# test-sensior-platiene.net
KiCad netlist of a schematic drawn in EAGLE
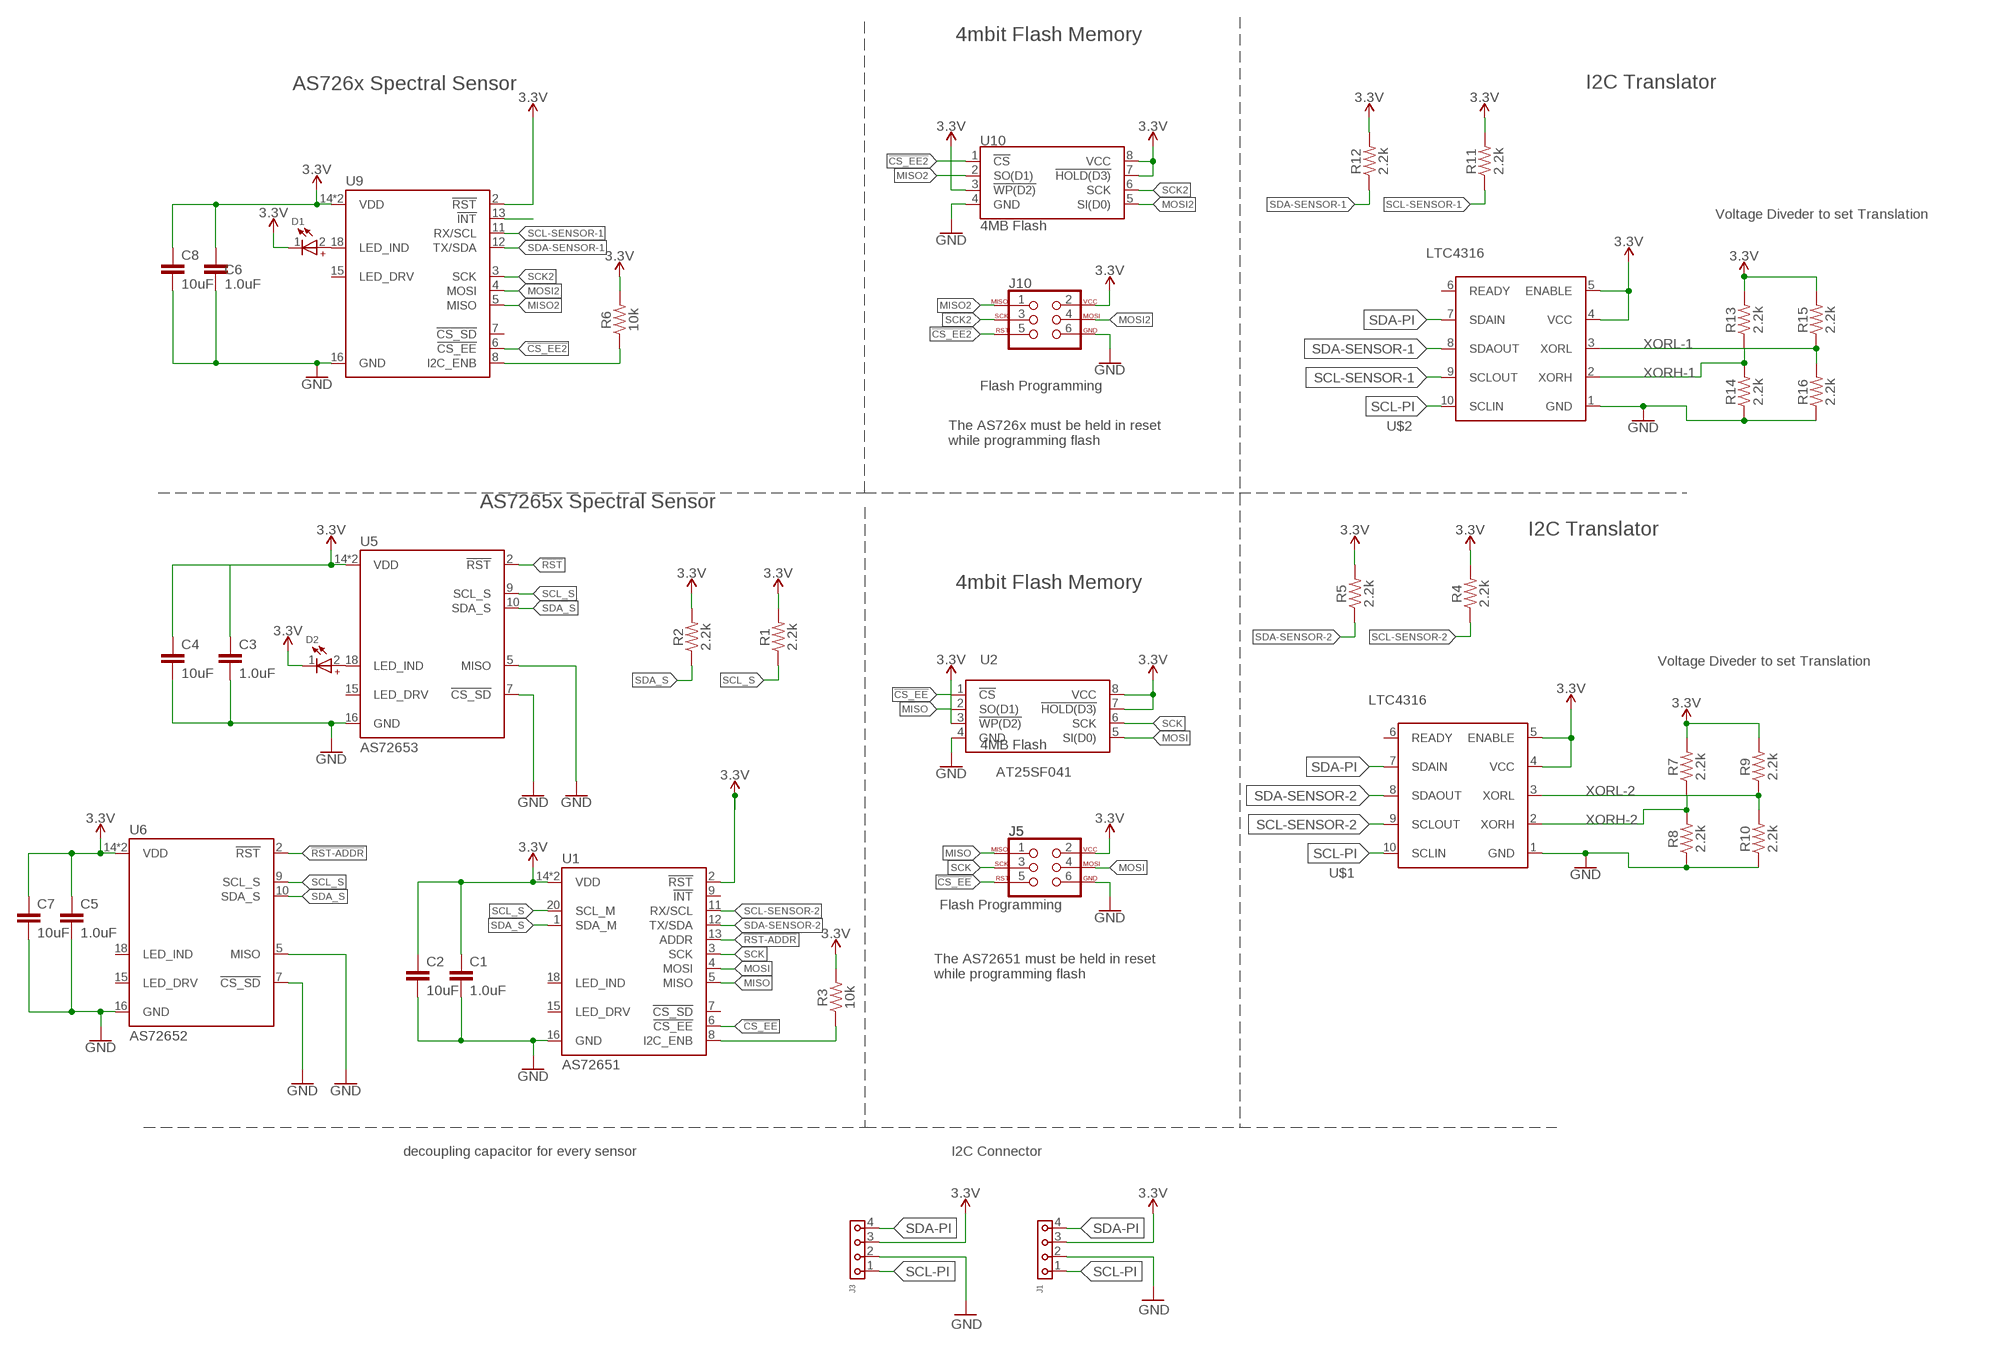
[diagram p0: schematic, sheet 1]

(export (version "E")
  (design (tool "Eeschema 10.0.6"))
  (components
    (comp (ref "C1")
      (value "1.0uF")
      (footprint "eagle-import:0603")
      (libsource (lib "eagle-import") (part "1.0UF-0603-16V-10%"))
    )
    (comp (ref "C2")
      (value "10uF")
      (footprint "eagle-import:0603")
      (libsource (lib "eagle-import") (part "10UF-0603-6.3V-20%"))
    )
    (comp (ref "C3")
      (value "1.0uF")
      (footprint "eagle-import:0603")
      (libsource (lib "eagle-import") (part "1.0UF-0603-16V-10%"))
    )
    (comp (ref "C4")
      (value "10uF")
      (footprint "eagle-import:0603")
      (libsource (lib "eagle-import") (part "10UF-0603-6.3V-20%"))
    )
    (comp (ref "C5")
      (value "1.0uF")
      (footprint "eagle-import:0603")
      (libsource (lib "eagle-import") (part "1.0UF-0603-16V-10%"))
    )
    (comp (ref "C6")
      (value "1.0uF")
      (footprint "eagle-import:0603")
      (libsource (lib "eagle-import") (part "1.0UF-0603-16V-10%"))
    )
    (comp (ref "C7")
      (value "10uF")
      (footprint "eagle-import:0603")
      (libsource (lib "eagle-import") (part "10UF-0603-6.3V-20%"))
    )
    (comp (ref "C8")
      (value "10uF")
      (footprint "eagle-import:0603")
      (libsource (lib "eagle-import") (part "10UF-0603-6.3V-20%"))
    )
    (comp (ref "D1")
      (value "WL-SMCW_1206_150120RS75000")
      (footprint "eagle-import:WL-SMCW_1206")
      (libsource (lib "eagle-import") (part "WL-SMCW_1206_150120RS75000"))
    )
    (comp (ref "D2")
      (value "WL-SMCW_1206_150120RS75000")
      (footprint "eagle-import:WL-SMCW_1206")
      (libsource (lib "eagle-import") (part "WL-SMCW_1206_150120RS75000"))
    )
    (comp (ref "J1")
      (value "6130XX11821_61300411821")
      (footprint "eagle-import:61300411821")
      (libsource (lib "eagle-import") (part "6130XX11821_61300411821"))
    )
    (comp (ref "J3")
      (value "6130XX11821_61300411821")
      (footprint "eagle-import:61300411821")
      (libsource (lib "eagle-import") (part "6130XX11821_61300411821"))
    )
    (comp (ref "J5")
      (value "Flash Programming")
      (footprint "eagle-import:2X3_TEST_POINTS")
      (libsource (lib "eagle-import") (part "AVR_SPI_PROG_3X2TESTPOINTS"))
    )
    (comp (ref "J10")
      (value "Flash Programming")
      (footprint "eagle-import:2X3_TEST_POINTS")
      (libsource (lib "eagle-import") (part "AVR_SPI_PROG_3X2TESTPOINTS"))
    )
    (comp (ref "R1")
      (value "2.2k")
      (footprint "eagle-import:0603")
      (libsource (lib "eagle-import") (part "2.2KOHM-0603-1/10W-1%"))
    )
    (comp (ref "R2")
      (value "2.2k")
      (footprint "eagle-import:0603")
      (libsource (lib "eagle-import") (part "2.2KOHM-0603-1/10W-1%"))
    )
    (comp (ref "R3")
      (value "10k")
      (footprint "eagle-import:0603")
      (libsource (lib "eagle-import") (part "10KOHM-0603-1/10W-1%"))
    )
    (comp (ref "R4")
      (value "2.2k")
      (footprint "eagle-import:0603")
      (libsource (lib "eagle-import") (part "2.2KOHM-0603-1/10W-1%"))
    )
    (comp (ref "R5")
      (value "2.2k")
      (footprint "eagle-import:0603")
      (libsource (lib "eagle-import") (part "2.2KOHM-0603-1/10W-1%"))
    )
    (comp (ref "R6")
      (value "10k")
      (footprint "eagle-import:0603")
      (libsource (lib "eagle-import") (part "10KOHM-0603-1/10W-1%"))
    )
    (comp (ref "R7")
      (value "2.2k")
      (footprint "eagle-import:0603")
      (libsource (lib "eagle-import") (part "2.2KOHM-0603-1/10W-1%"))
    )
    (comp (ref "R8")
      (value "2.2k")
      (footprint "eagle-import:0603")
      (libsource (lib "eagle-import") (part "2.2KOHM-0603-1/10W-1%"))
    )
    (comp (ref "R9")
      (value "2.2k")
      (footprint "eagle-import:0603")
      (libsource (lib "eagle-import") (part "2.2KOHM-0603-1/10W-1%"))
    )
    (comp (ref "R10")
      (value "2.2k")
      (footprint "eagle-import:0603")
      (libsource (lib "eagle-import") (part "2.2KOHM-0603-1/10W-1%"))
    )
    (comp (ref "R11")
      (value "2.2k")
      (footprint "eagle-import:0603")
      (libsource (lib "eagle-import") (part "2.2KOHM-0603-1/10W-1%"))
    )
    (comp (ref "R12")
      (value "2.2k")
      (footprint "eagle-import:0603")
      (libsource (lib "eagle-import") (part "2.2KOHM-0603-1/10W-1%"))
    )
    (comp (ref "R13")
      (value "2.2k")
      (footprint "eagle-import:0603")
      (libsource (lib "eagle-import") (part "2.2KOHM-0603-1/10W-1%"))
    )
    (comp (ref "R14")
      (value "2.2k")
      (footprint "eagle-import:0603")
      (libsource (lib "eagle-import") (part "2.2KOHM-0603-1/10W-1%"))
    )
    (comp (ref "R15")
      (value "2.2k")
      (footprint "eagle-import:0603")
      (libsource (lib "eagle-import") (part "2.2KOHM-0603-1/10W-1%"))
    )
    (comp (ref "R16")
      (value "2.2k")
      (footprint "eagle-import:0603")
      (libsource (lib "eagle-import") (part "2.2KOHM-0603-1/10W-1%"))
    )
    (comp (ref "U$1")
      (value "LTC4316")
      (footprint "eagle-import:MS-PACKAGE")
      (libsource (lib "eagle-import") (part "LTC4316"))
    )
    (comp (ref "U$2")
      (value "LTC4316")
      (footprint "eagle-import:MS-PACKAGE")
      (libsource (lib "eagle-import") (part "LTC4316"))
    )
    (comp (ref "U1")
      (value "AS72651")
      (footprint "eagle-import:LGA20")
      (libsource (lib "eagle-import") (part "AS72651"))
    )
    (comp (ref "U2")
      (value "4MB Flash")
      (footprint "eagle-import:SO08")
      (libsource (lib "eagle-import") (part "AT25SF041"))
    )
    (comp (ref "U5")
      (value "AS72653")
      (footprint "eagle-import:LGA20")
      (libsource (lib "eagle-import") (part "AS72653"))
    )
    (comp (ref "U6")
      (value "AS72652")
      (footprint "eagle-import:LGA20")
      (libsource (lib "eagle-import") (part "AS72652"))
    )
    (comp (ref "U9")
      (value "IR")
      (footprint "eagle-import:LGA20")
      (libsource (lib "eagle-import") (part "AS726XIR"))
    )
    (comp (ref "U10")
      (value "4MB Flash")
      (footprint "eagle-import:SO08")
      (libsource (lib "eagle-import") (part "AT25SF041"))
    )
  )
  (nets
    (net (code "1") (name "/XORH-1") (class "Default")
      (node (ref "R13") (pin "1") (pinfunction "1_1") (pintype "passive"))
      (node (ref "R14") (pin "2") (pinfunction "2_2") (pintype "passive"))
      (node (ref "U$2") (pin "2") (pinfunction "XORH_2") (pintype "bidirectional"))
    )
    (net (code "2") (name "/XORH-2") (class "Default")
      (node (ref "R7") (pin "1") (pinfunction "1_1") (pintype "passive"))
      (node (ref "R8") (pin "2") (pinfunction "2_2") (pintype "passive"))
      (node (ref "U$1") (pin "2") (pinfunction "XORH_2") (pintype "bidirectional"))
    )
    (net (code "3") (name "/XORL-1") (class "Default")
      (node (ref "R15") (pin "1") (pinfunction "1_1") (pintype "passive"))
      (node (ref "R16") (pin "2") (pinfunction "2_2") (pintype "passive"))
      (node (ref "U$2") (pin "3") (pinfunction "XORL_3") (pintype "bidirectional"))
    )
    (net (code "4") (name "/XORL-2") (class "Default")
      (node (ref "R10") (pin "2") (pinfunction "2_2") (pintype "passive"))
      (node (ref "R9") (pin "1") (pinfunction "1_1") (pintype "passive"))
      (node (ref "U$1") (pin "3") (pinfunction "XORL_3") (pintype "bidirectional"))
    )
    (net (code "5") (name "/~{CS_EE2}") (class "Default")
      (node (ref "J10") (pin "5") (pinfunction "5_5") (pintype "passive"))
      (node (ref "U10") (pin "1") (pinfunction "~{CS}_1") (pintype "bidirectional"))
      (node (ref "U9") (pin "6") (pinfunction "~{CS_EE}_6") (pintype "bidirectional"))
    )
    (net (code "6") (name "/~{CS_EE}") (class "Default")
      (node (ref "J5") (pin "5") (pinfunction "5_5") (pintype "passive"))
      (node (ref "U1") (pin "6") (pinfunction "~{CS_EE}_6") (pintype "bidirectional"))
      (node (ref "U2") (pin "1") (pinfunction "~{CS}_1") (pintype "bidirectional"))
    )
    (net (code "7") (name "/~{RST-ADDR}") (class "Default")
      (node (ref "U1") (pin "13") (pinfunction "ADDR_13") (pintype "bidirectional"))
      (node (ref "U6") (pin "2") (pinfunction "~{RST}_2") (pintype "bidirectional"))
    )
    (net (code "8") (name "/~{RST}") (class "Default")
      (node (ref "U5") (pin "2") (pinfunction "~{RST}_2") (pintype "bidirectional"))
    )
    (net (code "9") (name "3.3V") (class "Default")
      (node (ref "C1") (pin "1") (pinfunction "1_1") (pintype "passive"))
      (node (ref "C2") (pin "1") (pinfunction "1_1") (pintype "passive"))
      (node (ref "C3") (pin "1") (pinfunction "1_1") (pintype "passive"))
      (node (ref "C4") (pin "1") (pinfunction "1_1") (pintype "passive"))
      (node (ref "C5") (pin "1") (pinfunction "1_1") (pintype "passive"))
      (node (ref "C6") (pin "1") (pinfunction "1_1") (pintype "passive"))
      (node (ref "C7") (pin "1") (pinfunction "1_1") (pintype "passive"))
      (node (ref "C8") (pin "1") (pinfunction "1_1") (pintype "passive"))
      (node (ref "D1") (pin "1") (pinfunction "-_1") (pintype "passive"))
      (node (ref "D2") (pin "1") (pinfunction "-_1") (pintype "passive"))
      (node (ref "J1") (pin "3") (pinfunction "3_3") (pintype "passive"))
      (node (ref "J10") (pin "2") (pinfunction "2_2") (pintype "passive"))
      (node (ref "J3") (pin "3") (pinfunction "3_3") (pintype "passive"))
      (node (ref "J5") (pin "2") (pinfunction "2_2") (pintype "passive"))
      (node (ref "R1") (pin "2") (pinfunction "2_2") (pintype "passive"))
      (node (ref "R11") (pin "2") (pinfunction "2_2") (pintype "passive"))
      (node (ref "R12") (pin "2") (pinfunction "2_2") (pintype "passive"))
      (node (ref "R13") (pin "2") (pinfunction "2_2") (pintype "passive"))
      (node (ref "R15") (pin "2") (pinfunction "2_2") (pintype "passive"))
      (node (ref "R2") (pin "2") (pinfunction "2_2") (pintype "passive"))
      (node (ref "R3") (pin "2") (pinfunction "2_2") (pintype "passive"))
      (node (ref "R4") (pin "2") (pinfunction "2_2") (pintype "passive"))
      (node (ref "R5") (pin "2") (pinfunction "2_2") (pintype "passive"))
      (node (ref "R6") (pin "2") (pinfunction "2_2") (pintype "passive"))
      (node (ref "R7") (pin "2") (pinfunction "2_2") (pintype "passive"))
      (node (ref "R9") (pin "2") (pinfunction "2_2") (pintype "passive"))
      (node (ref "U$1") (pin "4") (pinfunction "VCC_4") (pintype "bidirectional"))
      (node (ref "U$1") (pin "5") (pinfunction "ENABLE_5") (pintype "bidirectional"))
      (node (ref "U$2") (pin "4") (pinfunction "VCC_4") (pintype "bidirectional"))
      (node (ref "U$2") (pin "5") (pinfunction "ENABLE_5") (pintype "bidirectional"))
      (node (ref "U1") (pin "14") (pinfunction "VDD_14") (pintype "bidirectional"))
      (node (ref "U1") (pin "17") (pinfunction "VDD_17") (pintype "bidirectional"))
      (node (ref "U1") (pin "2") (pinfunction "~{RST}_2") (pintype "bidirectional"))
      (node (ref "U10") (pin "3") (pinfunction "~{WP(D2})_3") (pintype "bidirectional"))
      (node (ref "U10") (pin "7") (pinfunction "~{HOLD(D3})_7") (pintype "bidirectional"))
      (node (ref "U10") (pin "8") (pinfunction "VCC_8") (pintype "bidirectional"))
      (node (ref "U2") (pin "3") (pinfunction "~{WP(D2})_3") (pintype "bidirectional"))
      (node (ref "U2") (pin "7") (pinfunction "~{HOLD(D3})_7") (pintype "bidirectional"))
      (node (ref "U2") (pin "8") (pinfunction "VCC_8") (pintype "bidirectional"))
      (node (ref "U5") (pin "14") (pinfunction "VDD_14") (pintype "bidirectional"))
      (node (ref "U5") (pin "17") (pinfunction "VDD_17") (pintype "bidirectional"))
      (node (ref "U6") (pin "14") (pinfunction "VDD_14") (pintype "bidirectional"))
      (node (ref "U6") (pin "17") (pinfunction "VDD_17") (pintype "bidirectional"))
      (node (ref "U9") (pin "14") (pinfunction "VDD_14") (pintype "bidirectional"))
      (node (ref "U9") (pin "17") (pinfunction "VDD_17") (pintype "bidirectional"))
      (node (ref "U9") (pin "2") (pinfunction "~{RST}_2") (pintype "bidirectional"))
    )
    (net (code "10") (name "GND") (class "Default")
      (node (ref "C1") (pin "2") (pinfunction "2_2") (pintype "passive"))
      (node (ref "C2") (pin "2") (pinfunction "2_2") (pintype "passive"))
      (node (ref "C3") (pin "2") (pinfunction "2_2") (pintype "passive"))
      (node (ref "C4") (pin "2") (pinfunction "2_2") (pintype "passive"))
      (node (ref "C5") (pin "2") (pinfunction "2_2") (pintype "passive"))
      (node (ref "C6") (pin "2") (pinfunction "2_2") (pintype "passive"))
      (node (ref "C7") (pin "2") (pinfunction "2_2") (pintype "passive"))
      (node (ref "C8") (pin "2") (pinfunction "2_2") (pintype "passive"))
      (node (ref "J1") (pin "2") (pinfunction "2_2") (pintype "passive"))
      (node (ref "J10") (pin "6") (pinfunction "6_6") (pintype "passive"))
      (node (ref "J3") (pin "2") (pinfunction "2_2") (pintype "passive"))
      (node (ref "J5") (pin "6") (pinfunction "6_6") (pintype "passive"))
      (node (ref "R10") (pin "1") (pinfunction "1_1") (pintype "passive"))
      (node (ref "R14") (pin "1") (pinfunction "1_1") (pintype "passive"))
      (node (ref "R16") (pin "1") (pinfunction "1_1") (pintype "passive"))
      (node (ref "R8") (pin "1") (pinfunction "1_1") (pintype "passive"))
      (node (ref "U$1") (pin "1") (pinfunction "GND_1") (pintype "bidirectional"))
      (node (ref "U$2") (pin "1") (pinfunction "GND_1") (pintype "bidirectional"))
      (node (ref "U1") (pin "16") (pinfunction "GND_16") (pintype "bidirectional"))
      (node (ref "U10") (pin "4") (pinfunction "GND_4") (pintype "bidirectional"))
      (node (ref "U2") (pin "4") (pinfunction "GND_4") (pintype "bidirectional"))
      (node (ref "U5") (pin "16") (pinfunction "GND_16") (pintype "bidirectional"))
      (node (ref "U5") (pin "5") (pinfunction "MISO_5") (pintype "bidirectional"))
      (node (ref "U5") (pin "7") (pinfunction "~{CS_SD}_7") (pintype "bidirectional"))
      (node (ref "U6") (pin "16") (pinfunction "GND_16") (pintype "bidirectional"))
      (node (ref "U6") (pin "5") (pinfunction "MISO_5") (pintype "bidirectional"))
      (node (ref "U6") (pin "7") (pinfunction "~{CS_SD}_7") (pintype "bidirectional"))
      (node (ref "U9") (pin "16") (pinfunction "GND_16") (pintype "bidirectional"))
    )
    (net (code "11") (name "MISO") (class "Default")
      (node (ref "J5") (pin "1") (pinfunction "1_1") (pintype "passive"))
      (node (ref "U1") (pin "5") (pinfunction "MISO_5") (pintype "bidirectional"))
      (node (ref "U2") (pin "2") (pinfunction "SO(D1)_2") (pintype "bidirectional"))
    )
    (net (code "12") (name "MISO2") (class "Default")
      (node (ref "J10") (pin "1") (pinfunction "1_1") (pintype "passive"))
      (node (ref "U10") (pin "2") (pinfunction "SO(D1)_2") (pintype "bidirectional"))
      (node (ref "U9") (pin "5") (pinfunction "MISO_5") (pintype "bidirectional"))
    )
    (net (code "13") (name "MOSI") (class "Default")
      (node (ref "J5") (pin "4") (pinfunction "4_4") (pintype "passive"))
      (node (ref "U1") (pin "4") (pinfunction "MOSI_4") (pintype "bidirectional"))
      (node (ref "U2") (pin "5") (pinfunction "SI(D0)_5") (pintype "bidirectional"))
    )
    (net (code "14") (name "MOSI2") (class "Default")
      (node (ref "J10") (pin "4") (pinfunction "4_4") (pintype "passive"))
      (node (ref "U10") (pin "5") (pinfunction "SI(D0)_5") (pintype "bidirectional"))
      (node (ref "U9") (pin "4") (pinfunction "MOSI_4") (pintype "bidirectional"))
    )
    (net (code "15") (name "Net-(D1-+)") (class "Default")
      (node (ref "D1") (pin "2") (pinfunction "+_2") (pintype "passive"))
      (node (ref "U9") (pin "18") (pinfunction "LED_IND_18") (pintype "bidirectional"))
    )
    (net (code "16") (name "Net-(D2-+)") (class "Default")
      (node (ref "D2") (pin "2") (pinfunction "+_2") (pintype "passive"))
      (node (ref "U5") (pin "18") (pinfunction "LED_IND_18") (pintype "bidirectional"))
    )
    (net (code "17") (name "Net-(U1-I2C_ENB)") (class "Default")
      (node (ref "R3") (pin "1") (pinfunction "1_1") (pintype "passive"))
      (node (ref "U1") (pin "8") (pinfunction "I2C_ENB_8") (pintype "bidirectional"))
    )
    (net (code "18") (name "Net-(U9-I2C_ENB)") (class "Default")
      (node (ref "R6") (pin "1") (pinfunction "1_1") (pintype "passive"))
      (node (ref "U9") (pin "8") (pinfunction "I2C_ENB_8") (pintype "bidirectional"))
    )
    (net (code "19") (name "SCK") (class "Default")
      (node (ref "J5") (pin "3") (pinfunction "3_3") (pintype "passive"))
      (node (ref "U1") (pin "3") (pinfunction "SCK_3") (pintype "bidirectional"))
      (node (ref "U2") (pin "6") (pinfunction "SCK_6") (pintype "bidirectional"))
    )
    (net (code "20") (name "SCK2") (class "Default")
      (node (ref "J10") (pin "3") (pinfunction "3_3") (pintype "passive"))
      (node (ref "U10") (pin "6") (pinfunction "SCK_6") (pintype "bidirectional"))
      (node (ref "U9") (pin "3") (pinfunction "SCK_3") (pintype "bidirectional"))
    )
    (net (code "21") (name "SCL-PI") (class "Default")
      (node (ref "J1") (pin "1") (pinfunction "1_1") (pintype "passive"))
      (node (ref "J3") (pin "1") (pinfunction "1_1") (pintype "passive"))
      (node (ref "U$1") (pin "10") (pinfunction "SCLIN_10") (pintype "bidirectional"))
      (node (ref "U$2") (pin "10") (pinfunction "SCLIN_10") (pintype "bidirectional"))
    )
    (net (code "22") (name "SCL-SENSOR-1") (class "Default")
      (node (ref "R11") (pin "1") (pinfunction "1_1") (pintype "passive"))
      (node (ref "U$2") (pin "9") (pinfunction "SCLOUT_9") (pintype "bidirectional"))
      (node (ref "U9") (pin "11") (pinfunction "RX/SCL_11") (pintype "bidirectional"))
    )
    (net (code "23") (name "SCL-SENSOR-2") (class "Default")
      (node (ref "R4") (pin "1") (pinfunction "1_1") (pintype "passive"))
      (node (ref "U$1") (pin "9") (pinfunction "SCLOUT_9") (pintype "bidirectional"))
      (node (ref "U1") (pin "11") (pinfunction "RX/SCL_11") (pintype "bidirectional"))
    )
    (net (code "24") (name "SCL_S") (class "Default")
      (node (ref "R1") (pin "1") (pinfunction "1_1") (pintype "passive"))
      (node (ref "U1") (pin "20") (pinfunction "SCL_M_20") (pintype "bidirectional"))
      (node (ref "U5") (pin "9") (pinfunction "SCL_S_9") (pintype "bidirectional"))
      (node (ref "U6") (pin "9") (pinfunction "SCL_S_9") (pintype "bidirectional"))
    )
    (net (code "25") (name "SDA-PI") (class "Default")
      (node (ref "J1") (pin "4") (pinfunction "4_4") (pintype "passive"))
      (node (ref "J3") (pin "4") (pinfunction "4_4") (pintype "passive"))
      (node (ref "U$1") (pin "7") (pinfunction "SDAIN_7") (pintype "bidirectional"))
      (node (ref "U$2") (pin "7") (pinfunction "SDAIN_7") (pintype "bidirectional"))
    )
    (net (code "26") (name "SDA-SENSOR-1") (class "Default")
      (node (ref "R12") (pin "1") (pinfunction "1_1") (pintype "passive"))
      (node (ref "U$2") (pin "8") (pinfunction "SDAOUT_8") (pintype "bidirectional"))
      (node (ref "U9") (pin "12") (pinfunction "TX/SDA_12") (pintype "bidirectional"))
    )
    (net (code "27") (name "SDA-SENSOR-2") (class "Default")
      (node (ref "R5") (pin "1") (pinfunction "1_1") (pintype "passive"))
      (node (ref "U$1") (pin "8") (pinfunction "SDAOUT_8") (pintype "bidirectional"))
      (node (ref "U1") (pin "12") (pinfunction "TX/SDA_12") (pintype "bidirectional"))
    )
    (net (code "28") (name "SDA_S") (class "Default")
      (node (ref "R2") (pin "1") (pinfunction "1_1") (pintype "passive"))
      (node (ref "U1") (pin "1") (pinfunction "SDA_M_1") (pintype "bidirectional"))
      (node (ref "U5") (pin "10") (pinfunction "SDA_S_10") (pintype "bidirectional"))
      (node (ref "U6") (pin "10") (pinfunction "SDA_S_10") (pintype "bidirectional"))
    )
    (net (code "29") (name "unconnected-(U$1-READY-Pad6)") (class "Default")
      (node (ref "U$1") (pin "6") (pinfunction "READY_6") (pintype "bidirectional"))
    )
    (net (code "30") (name "unconnected-(U$2-READY-Pad6)") (class "Default")
      (node (ref "U$2") (pin "6") (pinfunction "READY_6") (pintype "bidirectional"))
    )
    (net (code "31") (name "unconnected-(U1-LED_DRV-Pad15)") (class "Default")
      (node (ref "U1") (pin "15") (pinfunction "LED_DRV_15") (pintype "bidirectional"))
    )
    (net (code "32") (name "unconnected-(U1-LED_IND-Pad18)") (class "Default")
      (node (ref "U1") (pin "18") (pinfunction "LED_IND_18") (pintype "bidirectional"))
    )
    (net (code "33") (name "unconnected-(U1-~{CS_SD}-Pad7)") (class "Default")
      (node (ref "U1") (pin "7") (pinfunction "~{CS_SD}_7") (pintype "bidirectional"))
    )
    (net (code "34") (name "unconnected-(U1-~{INT}-Pad9)") (class "Default")
      (node (ref "U1") (pin "9") (pinfunction "~{INT}_9") (pintype "bidirectional"))
    )
    (net (code "35") (name "unconnected-(U5-LED_DRV-Pad15)") (class "Default")
      (node (ref "U5") (pin "15") (pinfunction "LED_DRV_15") (pintype "bidirectional"))
    )
    (net (code "36") (name "unconnected-(U6-LED_DRV-Pad15)") (class "Default")
      (node (ref "U6") (pin "15") (pinfunction "LED_DRV_15") (pintype "bidirectional"))
    )
    (net (code "37") (name "unconnected-(U6-LED_IND-Pad18)") (class "Default")
      (node (ref "U6") (pin "18") (pinfunction "LED_IND_18") (pintype "bidirectional"))
    )
    (net (code "38") (name "unconnected-(U9-LED_DRV-Pad15)") (class "Default")
      (node (ref "U9") (pin "15") (pinfunction "LED_DRV_15") (pintype "bidirectional"))
    )
    (net (code "39") (name "unconnected-(U9-~{CS_SD}-Pad7)") (class "Default")
      (node (ref "U9") (pin "7") (pinfunction "~{CS_SD}_7") (pintype "bidirectional"))
    )
    (net (code "40") (name "unconnected-(U9-~{INT}-Pad13)") (class "Default")
      (node (ref "U9") (pin "13") (pinfunction "~{INT}_13") (pintype "bidirectional"))
    )
  )
)
